# langProject.net
KiCad netlist of a schematic drawn in EAGLE
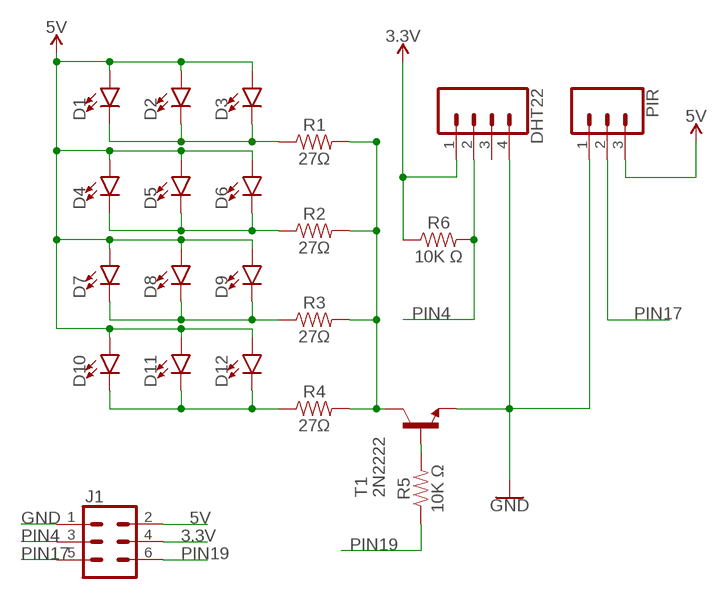
[diagram p0: schematic, sheet 1]

(export (version "E")
  (design (tool "Eeschema 10.0.6"))
  (components
    (comp (ref "D1")
      (value "LED5MM")
      (footprint "eagle-import:LED_5MM")
      (libsource (lib "eagle-import") (part "LED5MM"))
    )
    (comp (ref "D2")
      (value "LED5MM")
      (footprint "eagle-import:LED_5MM")
      (libsource (lib "eagle-import") (part "LED5MM"))
    )
    (comp (ref "D3")
      (value "LED5MM")
      (footprint "eagle-import:LED_5MM")
      (libsource (lib "eagle-import") (part "LED5MM"))
    )
    (comp (ref "D4")
      (value "LED5MM")
      (footprint "eagle-import:LED_5MM")
      (libsource (lib "eagle-import") (part "LED5MM"))
    )
    (comp (ref "D5")
      (value "LED5MM")
      (footprint "eagle-import:LED_5MM")
      (libsource (lib "eagle-import") (part "LED5MM"))
    )
    (comp (ref "D6")
      (value "LED5MM")
      (footprint "eagle-import:LED_5MM")
      (libsource (lib "eagle-import") (part "LED5MM"))
    )
    (comp (ref "D7")
      (value "LED5MM")
      (footprint "eagle-import:LED_5MM")
      (libsource (lib "eagle-import") (part "LED5MM"))
    )
    (comp (ref "D8")
      (value "LED5MM")
      (footprint "eagle-import:LED_5MM")
      (libsource (lib "eagle-import") (part "LED5MM"))
    )
    (comp (ref "D9")
      (value "LED5MM")
      (footprint "eagle-import:LED_5MM")
      (libsource (lib "eagle-import") (part "LED5MM"))
    )
    (comp (ref "D10")
      (value "LED5MM")
      (footprint "eagle-import:LED_5MM")
      (libsource (lib "eagle-import") (part "LED5MM"))
    )
    (comp (ref "D11")
      (value "LED5MM")
      (footprint "eagle-import:LED_5MM")
      (libsource (lib "eagle-import") (part "LED5MM"))
    )
    (comp (ref "D12")
      (value "LED5MM")
      (footprint "eagle-import:LED_5MM")
      (libsource (lib "eagle-import") (part "LED5MM"))
    )
    (comp (ref "DHT22")
      (value "CONN_04LONGPADS")
      (footprint "eagle-import:1X04_LONGPADS")
      (libsource (lib "eagle-import") (part "CONN_04LONGPADS"))
    )
    (comp (ref "J1")
      (value "CONN_03X2SHROUD")
      (footprint "eagle-import:2X3-SHROUDED")
      (libsource (lib "eagle-import") (part "CONN_03X2SHROUD"))
    )
    (comp (ref "PIR")
      (value "CONN_03LONGPADS")
      (footprint "eagle-import:1X03_LONGPADS")
      (libsource (lib "eagle-import") (part "CONN_03LONGPADS"))
    )
    (comp (ref "R1")
      (value "27Ω")
      (footprint "eagle-import:AXIAL-0.3-KIT")
      (libsource (lib "eagle-import") (part "10OHM-HORIZ_KIT-1/4W-1%"))
    )
    (comp (ref "R2")
      (value "27Ω")
      (footprint "eagle-import:AXIAL-0.3-KIT")
      (libsource (lib "eagle-import") (part "10OHM-HORIZ_KIT-1/4W-1%"))
    )
    (comp (ref "R3")
      (value "27Ω")
      (footprint "eagle-import:AXIAL-0.3-KIT")
      (libsource (lib "eagle-import") (part "10OHM-HORIZ_KIT-1/4W-1%"))
    )
    (comp (ref "R4")
      (value "27Ω")
      (footprint "eagle-import:AXIAL-0.3-KIT")
      (libsource (lib "eagle-import") (part "10OHM-HORIZ_KIT-1/4W-1%"))
    )
    (comp (ref "R5")
      (value "10K Ω")
      (footprint "eagle-import:AXIAL-0.3-KIT")
      (libsource (lib "eagle-import") (part "10OHM-HORIZ_KIT-1/4W-1%"))
    )
    (comp (ref "R6")
      (value "10K Ω")
      (footprint "eagle-import:AXIAL-0.3-KIT")
      (libsource (lib "eagle-import") (part "10OHM-HORIZ_KIT-1/4W-1%"))
    )
    (comp (ref "T1")
      (value "2N2222")
      (footprint "eagle-import:TO92-EBC-OVAL")
      (libsource (lib "eagle-import") (part "2N2222"))
    )
  )
  (nets
    (net (code "1") (name "/PIN4") (class "Default")
      (node (ref "DHT22") (pin "2") (pinfunction "2_2") (pintype "passive"))
      (node (ref "J1") (pin "3") (pinfunction "3_3") (pintype "bidirectional"))
      (node (ref "R6") (pin "P$2") (pinfunction "2_P$2") (pintype "passive"))
    )
    (net (code "2") (name "/PIN17") (class "Default")
      (node (ref "J1") (pin "5") (pinfunction "5_5") (pintype "bidirectional"))
      (node (ref "PIR") (pin "2") (pinfunction "2_2") (pintype "passive"))
    )
    (net (code "3") (name "/PIN19") (class "Default")
      (node (ref "J1") (pin "6") (pinfunction "6_6") (pintype "bidirectional"))
      (node (ref "R5") (pin "P$1") (pinfunction "1_P$1") (pintype "passive"))
    )
    (net (code "4") (name "3.3V") (class "Default")
      (node (ref "DHT22") (pin "1") (pinfunction "1_1") (pintype "passive"))
      (node (ref "J1") (pin "4") (pinfunction "4_4") (pintype "bidirectional"))
      (node (ref "R6") (pin "P$1") (pinfunction "1_P$1") (pintype "passive"))
    )
    (net (code "5") (name "5V") (class "Default")
      (node (ref "D1") (pin "A") (pinfunction "A_A") (pintype "passive"))
      (node (ref "D10") (pin "A") (pinfunction "A_A") (pintype "passive"))
      (node (ref "D11") (pin "A") (pinfunction "A_A") (pintype "passive"))
      (node (ref "D12") (pin "A") (pinfunction "A_A") (pintype "passive"))
      (node (ref "D2") (pin "A") (pinfunction "A_A") (pintype "passive"))
      (node (ref "D3") (pin "A") (pinfunction "A_A") (pintype "passive"))
      (node (ref "D4") (pin "A") (pinfunction "A_A") (pintype "passive"))
      (node (ref "D5") (pin "A") (pinfunction "A_A") (pintype "passive"))
      (node (ref "D6") (pin "A") (pinfunction "A_A") (pintype "passive"))
      (node (ref "D7") (pin "A") (pinfunction "A_A") (pintype "passive"))
      (node (ref "D8") (pin "A") (pinfunction "A_A") (pintype "passive"))
      (node (ref "D9") (pin "A") (pinfunction "A_A") (pintype "passive"))
      (node (ref "J1") (pin "2") (pinfunction "2_2") (pintype "bidirectional"))
      (node (ref "PIR") (pin "3") (pinfunction "3_3") (pintype "passive"))
    )
    (net (code "6") (name "GND") (class "Default")
      (node (ref "DHT22") (pin "4") (pinfunction "4_4") (pintype "passive"))
      (node (ref "J1") (pin "1") (pinfunction "1_1") (pintype "bidirectional"))
      (node (ref "PIR") (pin "1") (pinfunction "1_1") (pintype "passive"))
      (node (ref "T1") (pin "E") (pinfunction "E_E") (pintype "passive"))
    )
    (net (code "7") (name "Net-(D1-C)") (class "Default")
      (node (ref "D1") (pin "K") (pinfunction "C_K") (pintype "passive"))
      (node (ref "D2") (pin "K") (pinfunction "C_K") (pintype "passive"))
      (node (ref "D3") (pin "K") (pinfunction "C_K") (pintype "passive"))
      (node (ref "R1") (pin "P$1") (pinfunction "1_P$1") (pintype "passive"))
    )
    (net (code "8") (name "Net-(D4-C)") (class "Default")
      (node (ref "D4") (pin "K") (pinfunction "C_K") (pintype "passive"))
      (node (ref "D5") (pin "K") (pinfunction "C_K") (pintype "passive"))
      (node (ref "D6") (pin "K") (pinfunction "C_K") (pintype "passive"))
      (node (ref "R2") (pin "P$1") (pinfunction "1_P$1") (pintype "passive"))
    )
    (net (code "9") (name "Net-(D7-C)") (class "Default")
      (node (ref "D7") (pin "K") (pinfunction "C_K") (pintype "passive"))
      (node (ref "D8") (pin "K") (pinfunction "C_K") (pintype "passive"))
      (node (ref "D9") (pin "K") (pinfunction "C_K") (pintype "passive"))
      (node (ref "R3") (pin "P$1") (pinfunction "1_P$1") (pintype "passive"))
    )
    (net (code "10") (name "Net-(D10-C)") (class "Default")
      (node (ref "D10") (pin "K") (pinfunction "C_K") (pintype "passive"))
      (node (ref "D11") (pin "K") (pinfunction "C_K") (pintype "passive"))
      (node (ref "D12") (pin "K") (pinfunction "C_K") (pintype "passive"))
      (node (ref "R4") (pin "P$1") (pinfunction "1_P$1") (pintype "passive"))
    )
    (net (code "11") (name "Net-(R1-2)") (class "Default")
      (node (ref "R1") (pin "P$2") (pinfunction "2_P$2") (pintype "passive"))
      (node (ref "R2") (pin "P$2") (pinfunction "2_P$2") (pintype "passive"))
      (node (ref "R3") (pin "P$2") (pinfunction "2_P$2") (pintype "passive"))
      (node (ref "R4") (pin "P$2") (pinfunction "2_P$2") (pintype "passive"))
      (node (ref "T1") (pin "C") (pinfunction "C_C") (pintype "passive"))
    )
    (net (code "12") (name "Net-(R5-2)") (class "Default")
      (node (ref "R5") (pin "P$2") (pinfunction "2_P$2") (pintype "passive"))
      (node (ref "T1") (pin "B") (pinfunction "B_B") (pintype "passive"))
    )
    (net (code "13") (name "unconnected-(DHT22-Pad3)") (class "Default")
      (node (ref "DHT22") (pin "3") (pinfunction "3_3") (pintype "passive"))
    )
  )
)
